# Motor_Coil_Driver.net
KiCad netlist of a schematic drawn in EasyEDA
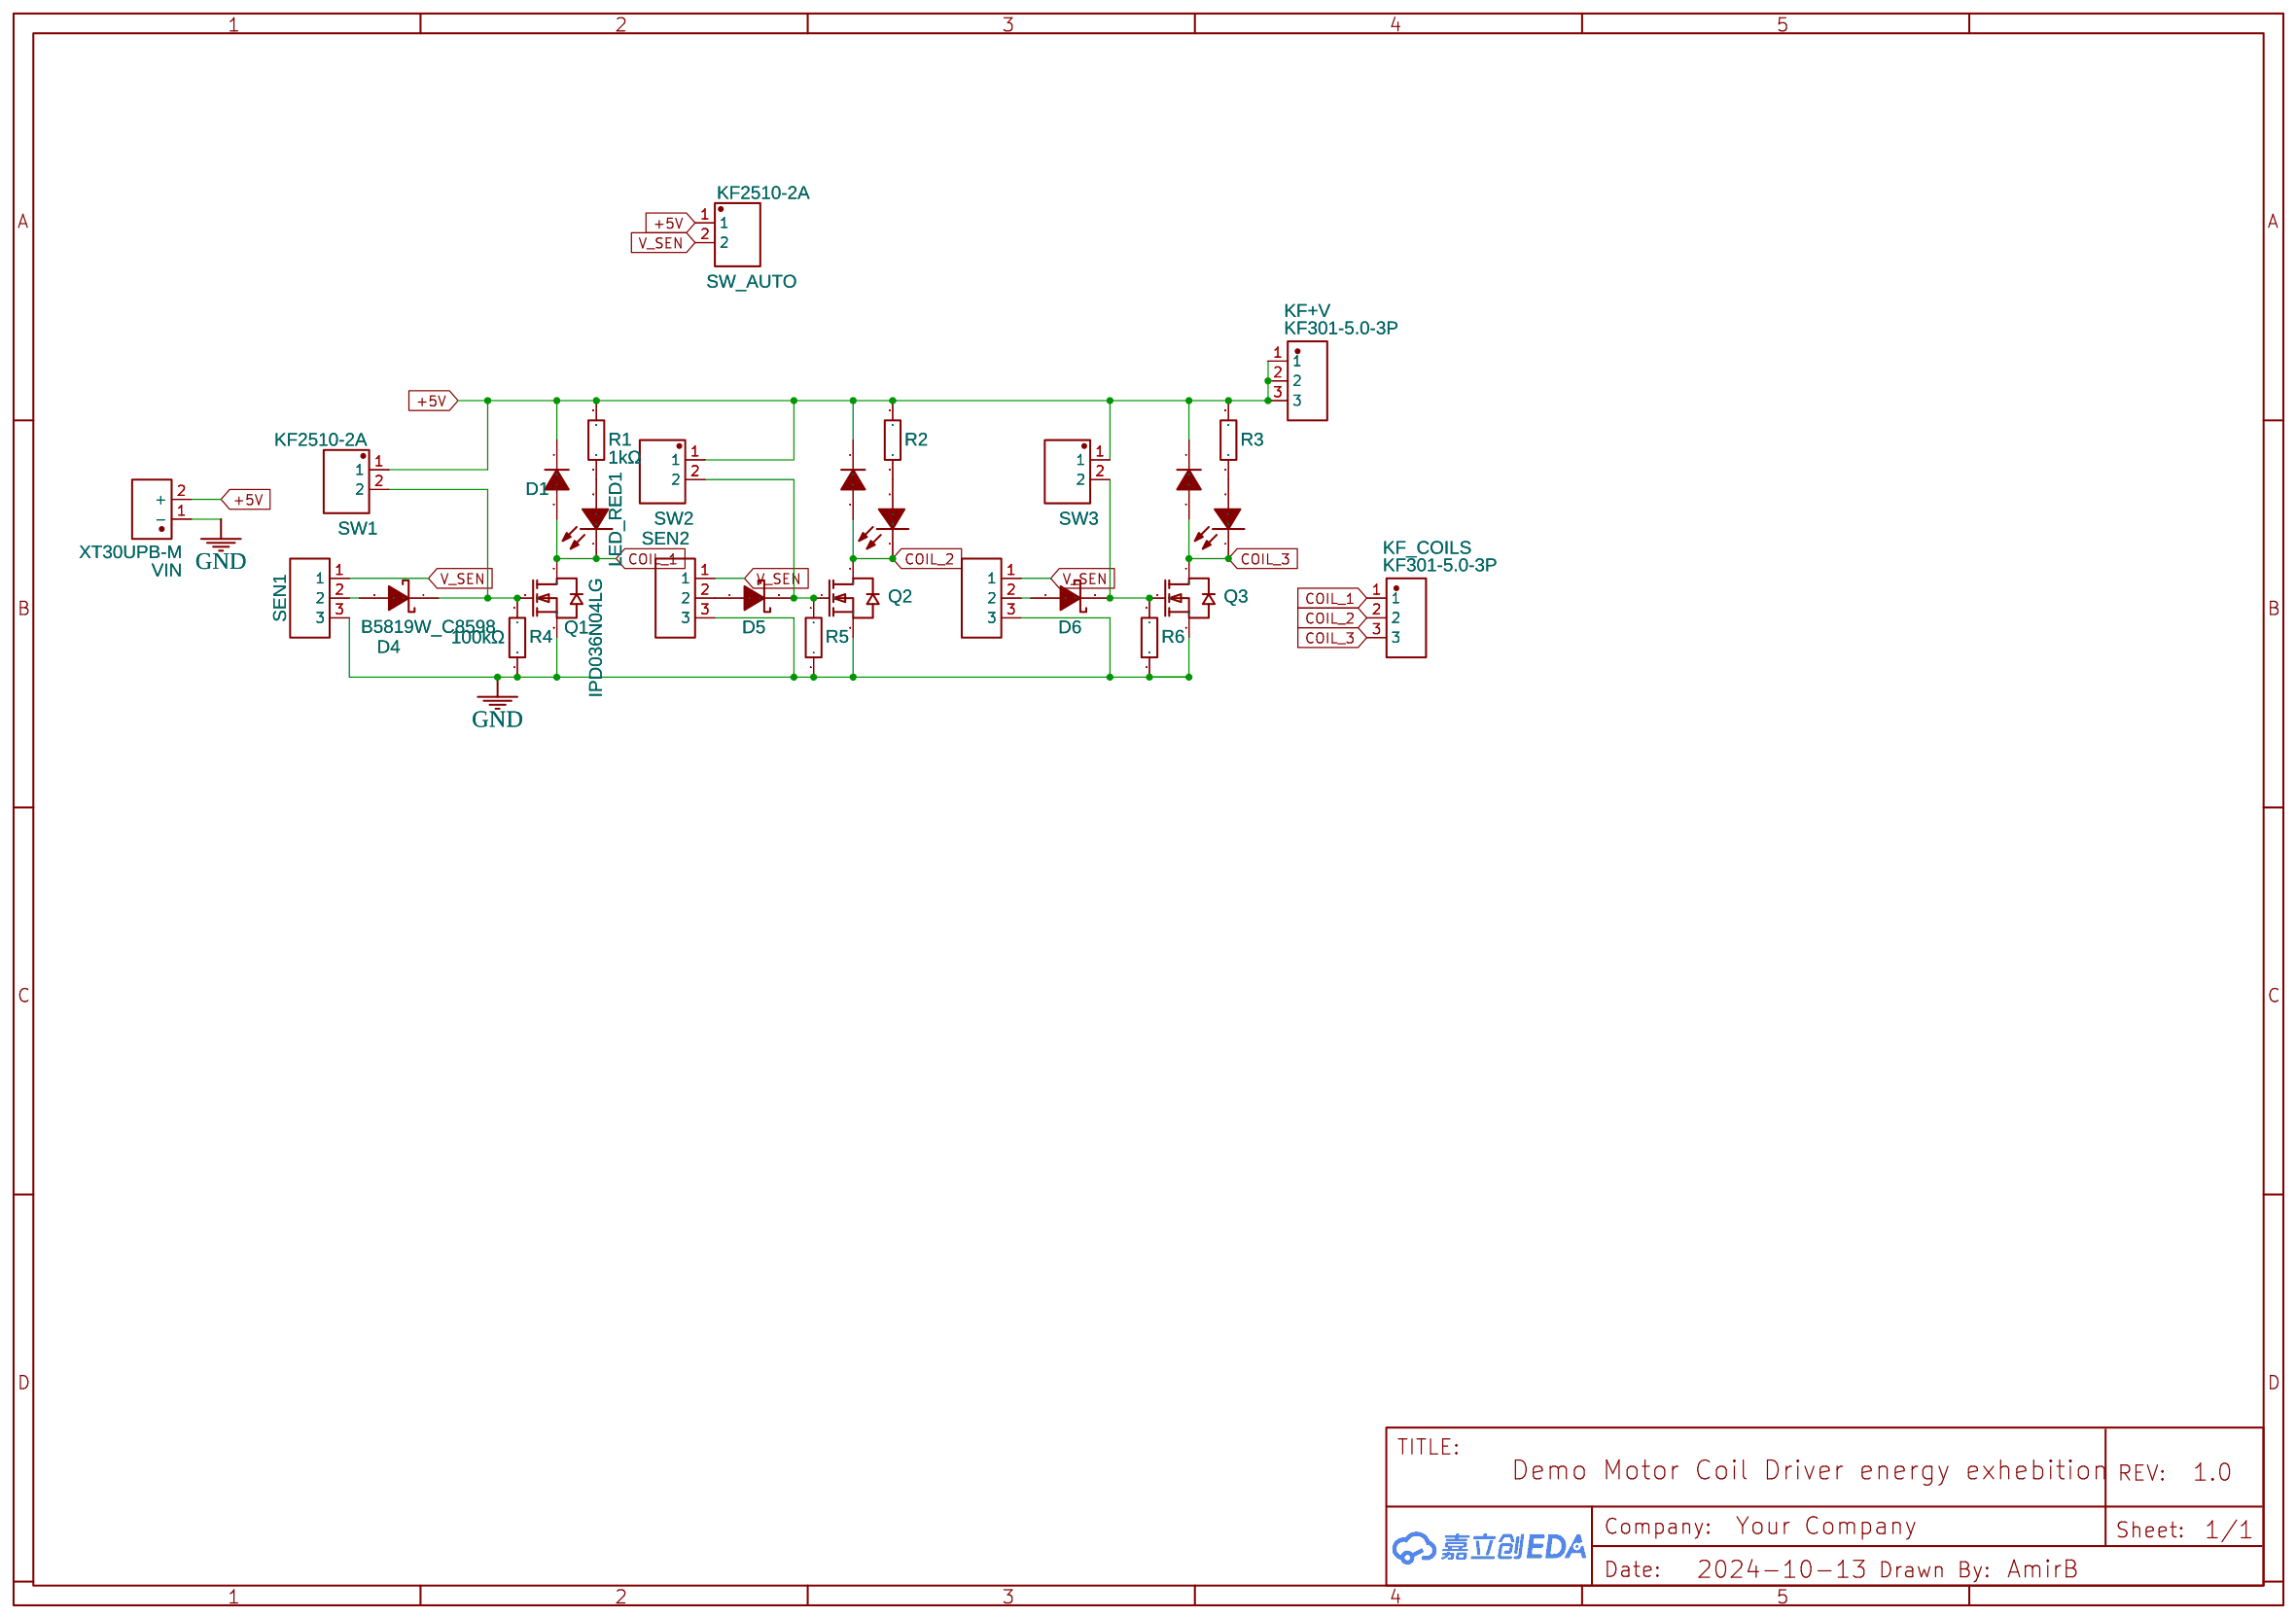
[diagram p0: schematic sheet]

(export (version "E")
  (design (tool "Eeschema 10.0.6"))
  (components
    (comp (ref "D1")
      (value "SM4007PL")
      (fields (field (name "Manufacturer") "MDD"))
      (libsource (lib "") (part "SM4007PL"))
    )
    (comp (ref "D2")
      (value "SM4007PL")
      (fields (field (name "Manufacturer") "MDD"))
      (libsource (lib "") (part "SM4007PL"))
    )
    (comp (ref "D3")
      (value "SM4007PL")
      (fields (field (name "Manufacturer") "MDD"))
      (libsource (lib "") (part "SM4007PL"))
    )
    (comp (ref "D4")
      (value "B5819W_C8598")
      (fields (field (name "Manufacturer Part") "B5819W SL") (field (name "Manufacturer") "CJ(江苏长电/长晶)"))
      (libsource (lib "") (part "B5819W_C8598"))
    )
    (comp (ref "D5")
      (value "B5819W_C8598")
      (fields (field (name "Manufacturer Part") "B5819W SL") (field (name "Manufacturer") "CJ(江苏长电/长晶)"))
      (libsource (lib "") (part "B5819W_C8598"))
    )
    (comp (ref "D6")
      (value "B5819W_C8598")
      (fields (field (name "Manufacturer Part") "B5819W SL") (field (name "Manufacturer") "CJ(江苏长电/长晶)"))
      (libsource (lib "") (part "B5819W_C8598"))
    )
    (comp (ref "KF+V")
      (value "KF301-5.0-3P")
      (fields (field (name "Manufacturer") "KEFA(科发)"))
      (libsource (lib "") (part "KF301-5.0-3P_1"))
    )
    (comp (ref "KF_COILS")
      (value "KF301-5.0-3P")
      (fields (field (name "Manufacturer") "KEFA(科发)"))
      (libsource (lib "") (part "KF301-5.0-3P"))
    )
    (comp (ref "LED_RED1")
      (value "KT-0603R")
      (fields (field (name "Manufacturer") "KENTO"))
      (libsource (lib "") (part "KT-0603R"))
    )
    (comp (ref "LED_RED2")
      (value "KT-0603R")
      (fields (field (name "Manufacturer") "KENTO"))
      (libsource (lib "") (part "KT-0603R"))
    )
    (comp (ref "LED_RED3")
      (value "KT-0603R")
      (fields (field (name "Manufacturer") "KENTO"))
      (libsource (lib "") (part "KT-0603R"))
    )
    (comp (ref "Q1")
      (value "IPD036N04LG")
      (fields
        (field (name "Manufacturer Part") "IPD036N04LG-VB")
        (field (name "Manufacturer") "VBsemi(微碧半导体)")
      )
      (libsource (lib "") (part "IPD036N04LG"))
    )
    (comp (ref "Q2")
      (value "IPD036N04LG")
      (fields
        (field (name "Manufacturer Part") "IPD036N04LG-VB")
        (field (name "Manufacturer") "VBsemi(微碧半导体)")
      )
      (libsource (lib "") (part "IPD036N04LG"))
    )
    (comp (ref "Q3")
      (value "IPD036N04LG")
      (fields
        (field (name "Manufacturer Part") "IPD036N04LG-VB")
        (field (name "Manufacturer") "VBsemi(微碧半导体)")
      )
      (libsource (lib "") (part "IPD036N04LG"))
    )
    (comp (ref "R1")
      (value "1kΩ")
      (fields (field (name "Manufacturer Part") "RC0603FR-071KL") (field (name "Manufacturer") "YAGEO(国巨)"))
      (libsource (lib "") (part "RC0603FR-071KL"))
    )
    (comp (ref "R2")
      (value "1kΩ")
      (fields (field (name "Manufacturer Part") "RC0603FR-071KL") (field (name "Manufacturer") "YAGEO(国巨)"))
      (libsource (lib "") (part "RC0603FR-071KL"))
    )
    (comp (ref "R3")
      (value "1kΩ")
      (fields (field (name "Manufacturer Part") "RC0603FR-071KL") (field (name "Manufacturer") "YAGEO(国巨)"))
      (libsource (lib "") (part "RC0603FR-071KL"))
    )
    (comp (ref "R4")
      (value "100kΩ")
      (fields
        (field (name "Manufacturer Part") "0603WAF1003T5E")
        (field (name "Manufacturer") "UNI-ROYAL(厚声)")
      )
      (libsource (lib "") (part "0603WAF1003T5E"))
    )
    (comp (ref "R5")
      (value "100kΩ")
      (fields
        (field (name "Manufacturer Part") "0603WAF1003T5E")
        (field (name "Manufacturer") "UNI-ROYAL(厚声)")
      )
      (libsource (lib "") (part "0603WAF1003T5E"))
    )
    (comp (ref "R6")
      (value "100kΩ")
      (fields
        (field (name "Manufacturer Part") "0603WAF1003T5E")
        (field (name "Manufacturer") "UNI-ROYAL(厚声)")
      )
      (libsource (lib "") (part "0603WAF1003T5E"))
    )
    (comp (ref "SEN1")
      (value "FK2510")
      (fields (field (name "Manufacturer Part") "2510-3A") (field (name "Manufacturer") "BOOMELE(博穆精密)"))
      (libsource (lib "") (part "kf2510_3A"))
    )
    (comp (ref "SEN2")
      (value "FK2510")
      (fields (field (name "Manufacturer Part") "2510-3A") (field (name "Manufacturer") "BOOMELE(博穆精密)"))
      (libsource (lib "") (part "kf2510_3A"))
    )
    (comp (ref "SEN3")
      (value "FK2510")
      (fields (field (name "Manufacturer Part") "2510-3A") (field (name "Manufacturer") "BOOMELE(博穆精密)"))
      (libsource (lib "") (part "kf2510_3A"))
    )
    (comp (ref "SW1")
      (value "KF2510-2A")
      (fields (field (name "BOM_Supplier Part") "C27543"))
      (libsource (lib "") (part "KF2510-2A"))
    )
    (comp (ref "SW2")
      (value "KF2510-2A")
      (fields (field (name "BOM_Supplier Part") "C27543"))
      (libsource (lib "") (part "KF2510-2A"))
    )
    (comp (ref "SW3")
      (value "KF2510-2A")
      (fields (field (name "BOM_Supplier Part") "C27543"))
      (libsource (lib "") (part "KF2510-2A"))
    )
    (comp (ref "SW_AUTO")
      (value "KF2510-2A")
      (fields (field (name "BOM_Supplier Part") "C27543"))
      (libsource (lib "") (part "KF2510-2A_1"))
    )
    (comp (ref "VIN")
      (value "XT30UPB-M")
      (fields (field (name "Manufacturer") "AMASS(艾迈斯)"))
      (libsource (lib "") (part "XT30UPB-M"))
    )
  )
  (nets
    (net (code "1") (name "+5V") (class "Default")
      (node (ref "D1") (pin "1") (pinfunction "C_1") (pintype "unspecified"))
      (node (ref "D2") (pin "1") (pinfunction "C_1") (pintype "unspecified"))
      (node (ref "D3") (pin "1") (pinfunction "C_1") (pintype "unspecified"))
      (node (ref "KF+V") (pin "1") (pinfunction "1_1") (pintype "unspecified"))
      (node (ref "KF+V") (pin "2") (pinfunction "2_2") (pintype "unspecified"))
      (node (ref "KF+V") (pin "3") (pinfunction "3_3") (pintype "unspecified"))
      (node (ref "R1") (pin "2") (pinfunction "2_2") (pintype "input"))
      (node (ref "R2") (pin "2") (pinfunction "2_2") (pintype "input"))
      (node (ref "R3") (pin "2") (pinfunction "2_2") (pintype "input"))
      (node (ref "SW1") (pin "1") (pinfunction "1_1") (pintype "unspecified"))
      (node (ref "SW2") (pin "1") (pinfunction "1_1") (pintype "unspecified"))
      (node (ref "SW3") (pin "1") (pinfunction "1_1") (pintype "unspecified"))
      (node (ref "SW_AUTO") (pin "1") (pinfunction "1_1") (pintype "unspecified"))
      (node (ref "VIN") (pin "2") (pinfunction "+_2") (pintype "unspecified"))
    )
    (net (code "2") (name "COIL_1") (class "Default")
      (node (ref "D1") (pin "2") (pinfunction "A_2") (pintype "unspecified"))
      (node (ref "KF_COILS") (pin "1") (pinfunction "1_1") (pintype "unspecified"))
      (node (ref "LED_RED1") (pin "1") (pinfunction "K_1") (pintype "unspecified"))
      (node (ref "Q1") (pin "2") (pinfunction "D_2") (pintype "unspecified"))
    )
    (net (code "3") (name "COIL_2") (class "Default")
      (node (ref "D2") (pin "2") (pinfunction "A_2") (pintype "unspecified"))
      (node (ref "KF_COILS") (pin "2") (pinfunction "2_2") (pintype "unspecified"))
      (node (ref "LED_RED2") (pin "1") (pinfunction "K_1") (pintype "unspecified"))
      (node (ref "Q2") (pin "2") (pinfunction "D_2") (pintype "unspecified"))
    )
    (net (code "4") (name "COIL_3") (class "Default")
      (node (ref "D3") (pin "2") (pinfunction "A_2") (pintype "unspecified"))
      (node (ref "KF_COILS") (pin "3") (pinfunction "3_3") (pintype "unspecified"))
      (node (ref "LED_RED3") (pin "1") (pinfunction "K_1") (pintype "unspecified"))
      (node (ref "Q3") (pin "2") (pinfunction "D_2") (pintype "unspecified"))
    )
    (net (code "5") (name "GND") (class "Default")
      (node (ref "Q1") (pin "3") (pinfunction "S_3") (pintype "unspecified"))
      (node (ref "Q2") (pin "3") (pinfunction "S_3") (pintype "unspecified"))
      (node (ref "Q3") (pin "3") (pinfunction "S_3") (pintype "unspecified"))
      (node (ref "R4") (pin "1") (pinfunction "1_1") (pintype "input"))
      (node (ref "R5") (pin "1") (pinfunction "1_1") (pintype "input"))
      (node (ref "R6") (pin "1") (pinfunction "1_1") (pintype "input"))
      (node (ref "SEN1") (pin "3") (pinfunction "3_3") (pintype "unspecified"))
      (node (ref "SEN2") (pin "3") (pinfunction "3_3") (pintype "unspecified"))
      (node (ref "SEN3") (pin "3") (pinfunction "3_3") (pintype "unspecified"))
      (node (ref "VIN") (pin "1") (pinfunction "-_1") (pintype "unspecified"))
    )
    (net (code "6") (name "Net-(D4-+)") (class "Default")
      (node (ref "D4") (pin "2") (pinfunction "+_2") (pintype "unspecified"))
      (node (ref "SEN1") (pin "2") (pinfunction "2_2") (pintype "unspecified"))
    )
    (net (code "7") (name "Net-(D4--)") (class "Default")
      (node (ref "D4") (pin "1") (pinfunction "-_1") (pintype "unspecified"))
      (node (ref "Q1") (pin "1") (pinfunction "G_1") (pintype "unspecified"))
      (node (ref "R4") (pin "2") (pinfunction "2_2") (pintype "input"))
      (node (ref "SW1") (pin "2") (pinfunction "2_2") (pintype "unspecified"))
    )
    (net (code "8") (name "Net-(D5-+)") (class "Default")
      (node (ref "D5") (pin "2") (pinfunction "+_2") (pintype "unspecified"))
      (node (ref "SEN2") (pin "2") (pinfunction "2_2") (pintype "unspecified"))
    )
    (net (code "9") (name "Net-(D5--)") (class "Default")
      (node (ref "D5") (pin "1") (pinfunction "-_1") (pintype "unspecified"))
      (node (ref "Q2") (pin "1") (pinfunction "G_1") (pintype "unspecified"))
      (node (ref "R5") (pin "2") (pinfunction "2_2") (pintype "input"))
      (node (ref "SW2") (pin "2") (pinfunction "2_2") (pintype "unspecified"))
    )
    (net (code "10") (name "Net-(D6-+)") (class "Default")
      (node (ref "D6") (pin "2") (pinfunction "+_2") (pintype "unspecified"))
      (node (ref "SEN3") (pin "2") (pinfunction "2_2") (pintype "unspecified"))
    )
    (net (code "11") (name "Net-(D6--)") (class "Default")
      (node (ref "D6") (pin "1") (pinfunction "-_1") (pintype "unspecified"))
      (node (ref "Q3") (pin "1") (pinfunction "G_1") (pintype "unspecified"))
      (node (ref "R6") (pin "2") (pinfunction "2_2") (pintype "input"))
      (node (ref "SW3") (pin "2") (pinfunction "2_2") (pintype "unspecified"))
    )
    (net (code "12") (name "Net-(LED_RED1-A)") (class "Default")
      (node (ref "LED_RED1") (pin "2") (pinfunction "A_2") (pintype "unspecified"))
      (node (ref "R1") (pin "1") (pinfunction "1_1") (pintype "input"))
    )
    (net (code "13") (name "Net-(LED_RED2-A)") (class "Default")
      (node (ref "LED_RED2") (pin "2") (pinfunction "A_2") (pintype "unspecified"))
      (node (ref "R2") (pin "1") (pinfunction "1_1") (pintype "input"))
    )
    (net (code "14") (name "Net-(LED_RED3-A)") (class "Default")
      (node (ref "LED_RED3") (pin "2") (pinfunction "A_2") (pintype "unspecified"))
      (node (ref "R3") (pin "1") (pinfunction "1_1") (pintype "input"))
    )
    (net (code "15") (name "V_SEN") (class "Default")
      (node (ref "SEN1") (pin "1") (pinfunction "1_1") (pintype "unspecified"))
      (node (ref "SEN2") (pin "1") (pinfunction "1_1") (pintype "unspecified"))
      (node (ref "SEN3") (pin "1") (pinfunction "1_1") (pintype "unspecified"))
      (node (ref "SW_AUTO") (pin "2") (pinfunction "2_2") (pintype "unspecified"))
    )
  )
)
